# Flight_Controller3.net
KiCad netlist of a schematic drawn in Altium Designer
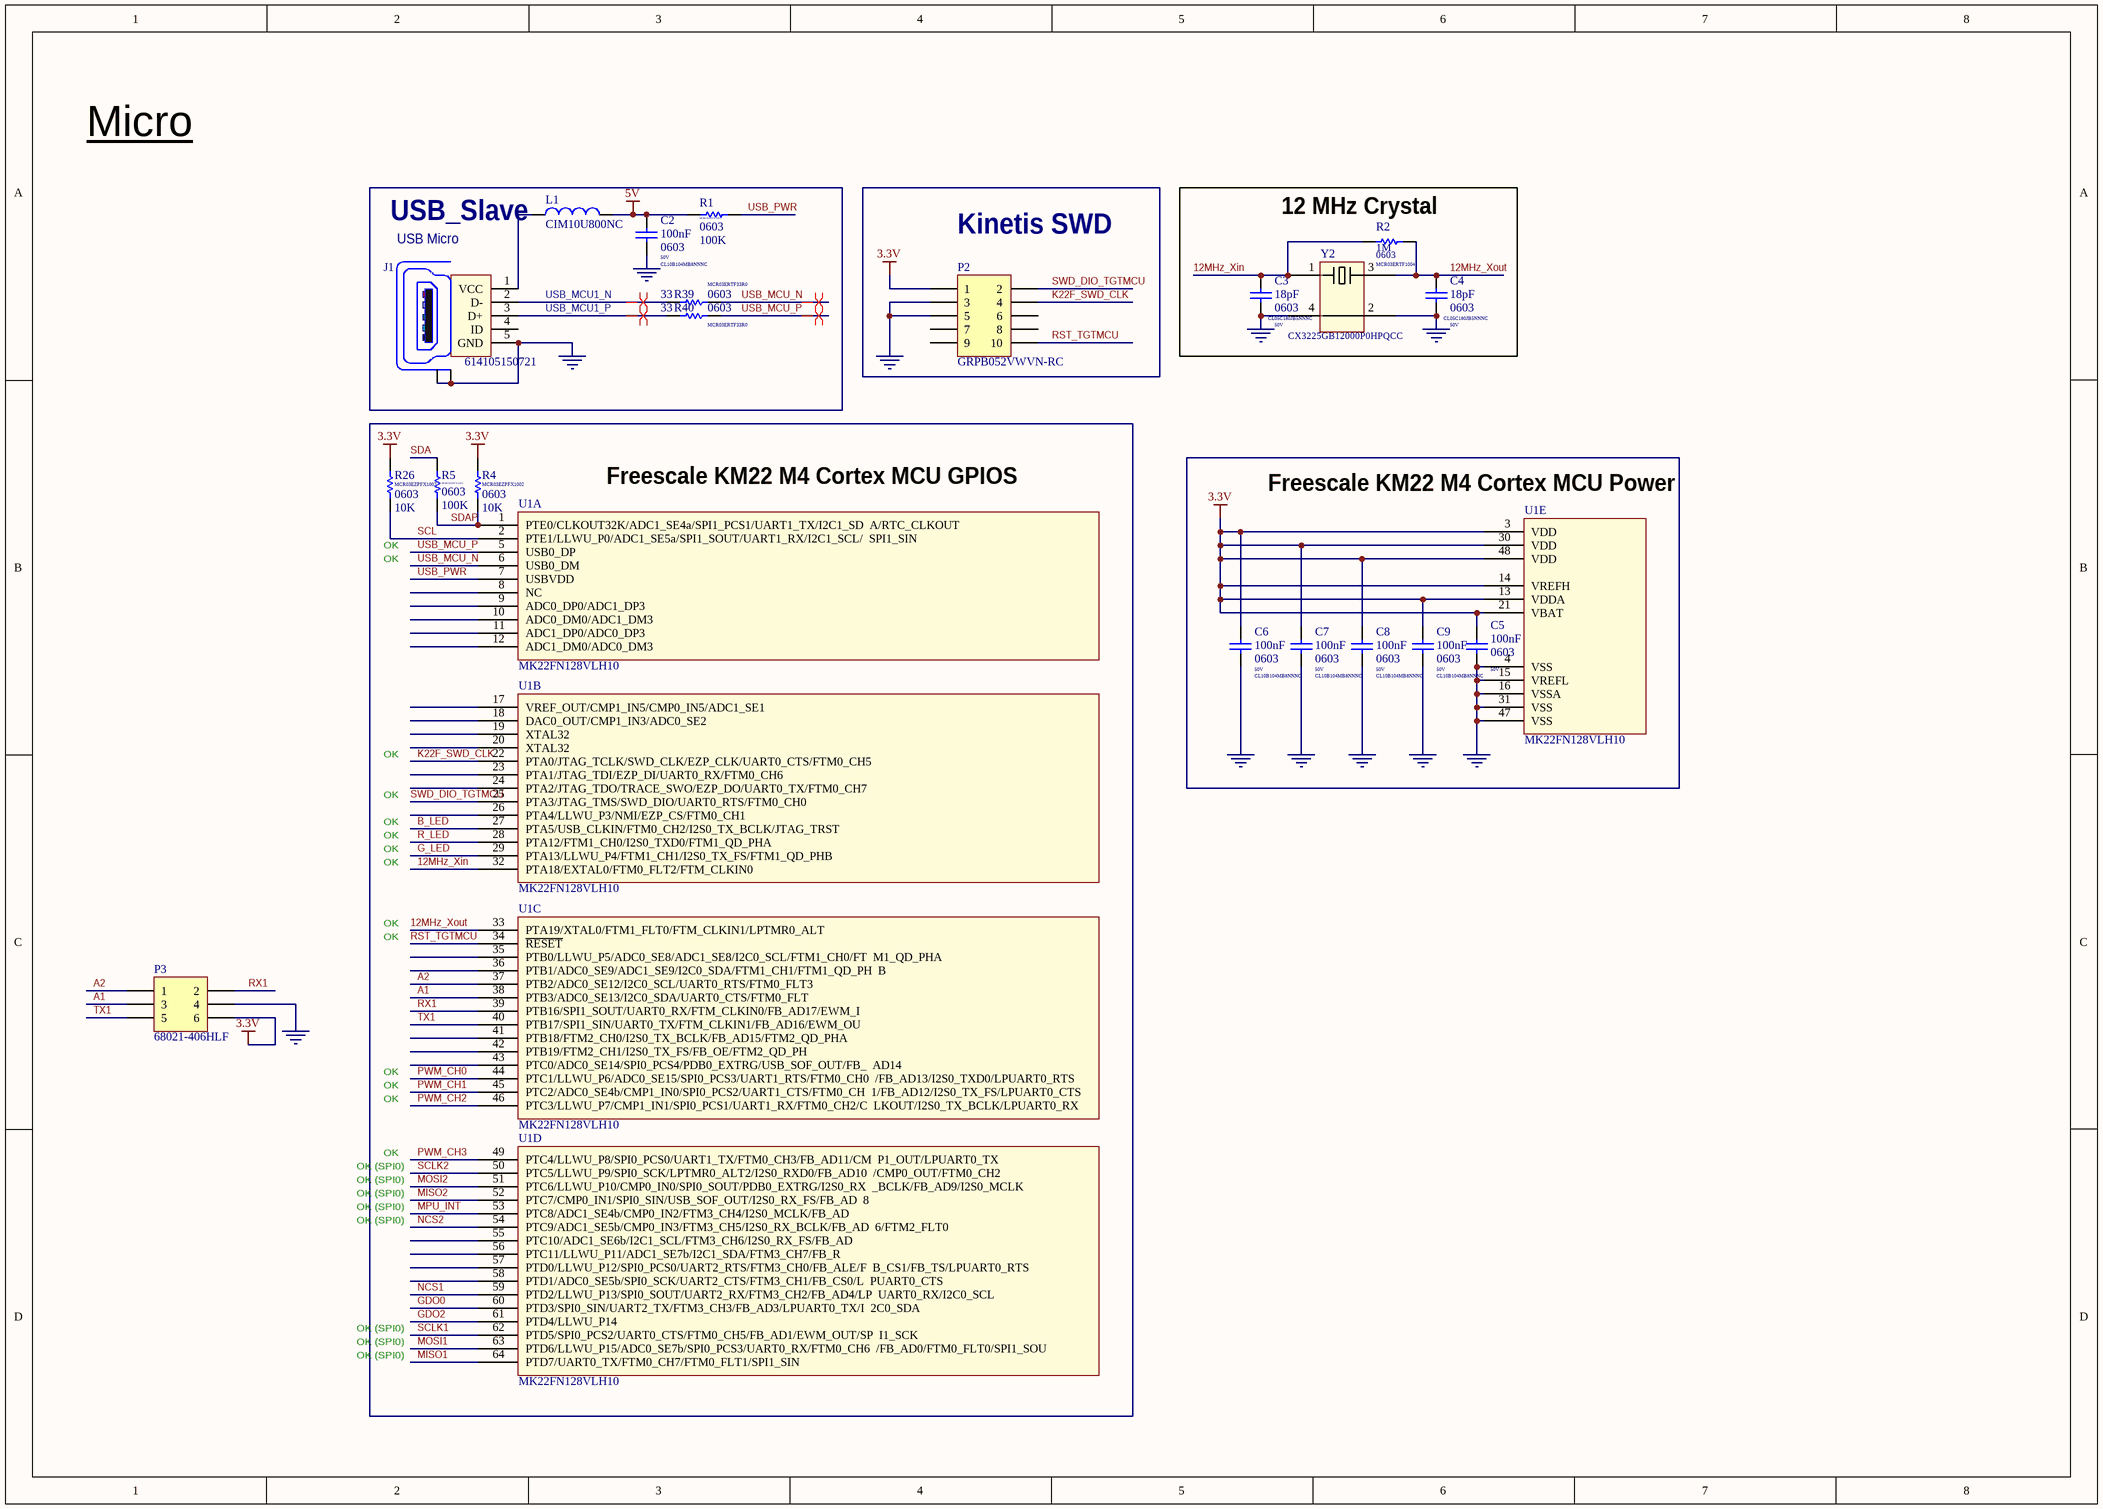
[diagram p0: Flight_Controller3.SchDoc]

(export (version "E")
  (design (tool "Eeschema 10.0.6"))
  (components
    (comp (ref "C2")
      (value "CL10B104MB8NNNC")
      (footprint "1608[0603]C")
      (description "Capacitor (Semiconductor SIM Model)")
      (fields
        (field (name "PACKAGEREFERENCE") "0603")
        (field (name "ALTIUM_VALUE") "100nF")
        (field (name "VOLTAGE") "50V")
      )
      (libsource (lib "Miscellaneous Devices") (part "Cap Semi"))
    )
    (comp (ref "C3")
      (value "CL05C180JB5NNNC")
      (footprint "1608[0603]C")
      (description "Capacitor (Semiconductor SIM Model)")
      (fields
        (field (name "PACKAGEREFERENCE") "0603")
        (field (name "ALTIUM_VALUE") "18pF")
        (field (name "VOLTAGE") "50V")
      )
      (libsource (lib "Miscellaneous Devices") (part "Cap Semi"))
    )
    (comp (ref "C4")
      (value "CL05C180JB5NNNC")
      (footprint "1608[0603]C")
      (description "Capacitor (Semiconductor SIM Model)")
      (fields
        (field (name "PACKAGEREFERENCE") "0603")
        (field (name "ALTIUM_VALUE") "18pF")
        (field (name "VOLTAGE") "50V")
      )
      (libsource (lib "Miscellaneous Devices") (part "Cap Semi"))
    )
    (comp (ref "C5")
      (value "100nF")
      (footprint "1608[0603]C")
      (description "Capacitor (Semiconductor SIM Model)")
      (fields
        (field (name "PACKAGEREFERENCE") "0603")
        (field (name "PART_NUMBER") "CL10B104MB8NNNC")
        (field (name "VOLTAGE") "50V")
      )
      (libsource (lib "Miscellaneous Devices") (part "Cap Semi"))
    )
    (comp (ref "C6")
      (value "CL10B104MB8NNNC")
      (footprint "1608[0603]C")
      (description "Capacitor (Semiconductor SIM Model)")
      (fields
        (field (name "PACKAGEREFERENCE") "0603")
        (field (name "ALTIUM_VALUE") "100nF")
        (field (name "VOLTAGE") "50V")
      )
      (libsource (lib "Miscellaneous Devices") (part "Cap Semi"))
    )
    (comp (ref "C7")
      (value "CL10B104MB8NNNC")
      (footprint "1608[0603]C")
      (description "Capacitor (Semiconductor SIM Model)")
      (fields
        (field (name "PACKAGEREFERENCE") "0603")
        (field (name "ALTIUM_VALUE") "100nF")
        (field (name "VOLTAGE") "50V")
      )
      (libsource (lib "Miscellaneous Devices") (part "Cap Semi"))
    )
    (comp (ref "C8")
      (value "CL10B104MB8NNNC")
      (footprint "1608[0603]C")
      (description "Capacitor (Semiconductor SIM Model)")
      (fields
        (field (name "PACKAGEREFERENCE") "0603")
        (field (name "ALTIUM_VALUE") "100nF")
        (field (name "VOLTAGE") "50V")
      )
      (libsource (lib "Miscellaneous Devices") (part "Cap Semi"))
    )
    (comp (ref "C9")
      (value "CL10B104MB8NNNC")
      (footprint "1608[0603]C")
      (description "Capacitor (Semiconductor SIM Model)")
      (fields
        (field (name "PACKAGEREFERENCE") "0603")
        (field (name "ALTIUM_VALUE") "100nF")
        (field (name "VOLTAGE") "50V")
      )
      (libsource (lib "Miscellaneous Devices") (part "Cap Semi"))
    )
    (comp (ref "J1")
      (value "614105150721")
      (footprint "USB_Micro_Vertical")
      (description "WR-COM_USB_Micro Type B_Vertical_THT")
      (fields
        (field (name "MANUFACTURER") "Würth Elektronik eiSos GmbH")
        (field (name "CREATED BY") "Karrer Zheng")
      )
      (libsource (lib "614105150721") (part "WR-Communication Connectors 614105150721"))
    )
    (comp (ref "L1")
      (value "CIM10U800NC")
      (footprint "1608[0603]L")
      (description "Inductor")
      (libsource (lib "Miscellaneous Devices") (part "Inductor"))
    )
    (comp (ref "P2")
      (value "GRPB052VWVN-RC")
      (footprint "MHDR2X5")
      (description "Header, 5-Pin, Dual row")
      (fields (field (name "PUBLISHER") "Altium Limited"))
      (libsource (lib "Miscellaneous Connectors") (part "Header 5X2"))
    )
    (comp (ref "P3")
      (value "68021-406HLF")
      (footprint "HDR2X3_3D2")
      (description "Header, 3-Pin, Dual row")
      (fields (field (name "PUBLISHER") "Altium Limited"))
      (libsource (lib "Miscellaneous Connectors") (part "Header 3X2"))
    )
    (comp (ref "R1")
      (value "MCR03EZPFX1003")
      (footprint "1608[0603]R")
      (description "Resistor")
      (fields
        (field (name "PACKAGEREFERENCE") "0603")
        (field (name "ALTIUM_VALUE") "100K")
        (field (name "PART_NUMBER") "MCR03ERTJ104")
      )
      (libsource (lib "Miscellaneous Devices") (part "Res1"))
    )
    (comp (ref "R2")
      (value "MCR03ERTF1004")
      (footprint "1608[0603]R")
      (description "Resistor")
      (fields (field (name "ALTIUM_VALUE") "1M") (field (name "PACKAGEREFERENCE") "0603"))
      (libsource (lib "Miscellaneous Devices") (part "Res1"))
    )
    (comp (ref "R4")
      (value "MCR03EZPFX1002")
      (footprint "1608[0603]R")
      (description "Resistor")
      (fields
        (field (name "PACKAGEREFERENCE") "0603")
        (field (name "ALTIUM_VALUE") "10K")
        (field (name "PART_NUMBER") "MCR03ERTJ102")
      )
      (libsource (lib "Miscellaneous Devices") (part "Res1"))
    )
    (comp (ref "R5")
      (value "MCR03EZPFX1003")
      (footprint "1608[0603]R")
      (description "Resistor")
      (fields
        (field (name "PACKAGEREFERENCE") "0603")
        (field (name "ALTIUM_VALUE") "100K")
        (field (name "PART_NUMBER") "MCR03ERTJ104")
      )
      (libsource (lib "Miscellaneous Devices") (part "Res1"))
    )
    (comp (ref "R26")
      (value "MCR03EZPFX1002")
      (footprint "1608[0603]R")
      (description "Resistor")
      (fields
        (field (name "PACKAGEREFERENCE") "0603")
        (field (name "ALTIUM_VALUE") "10K")
        (field (name "PART_NUMBER") "MCR03ERTJ102")
      )
      (libsource (lib "Miscellaneous Devices") (part "Res1"))
    )
    (comp (ref "R39")
      (value "MCR03ERTF33R0")
      (footprint "1608[0603]R")
      (description "Resistor")
      (fields (field (name "PACKAGEREFERENCE") "0603") (field (name "ALTIUM_VALUE") "33"))
      (libsource (lib "Miscellaneous Devices") (part "Res1"))
    )
    (comp (ref "R40")
      (value "MCR03ERTF33R0")
      (footprint "1608[0603]R")
      (description "Resistor")
      (fields
        (field (name "PACKAGEREFERENCE") "0603")
        (field (name "ALTIUM_VALUE") "33")
        (field (name "PART_NUMBER") "MCR03ERTJ102")
      )
      (libsource (lib "Miscellaneous Devices") (part "Res1"))
    )
    (comp (ref "U1")
      (value "MK22FN128VLH10")
      (footprint "LQFP64_10mm_0.5mm")
      (description "MK22FN128VLH10 MCU")
      (libsource (lib "Flight_Controller") (part "MK22FN128VLH10"))
    )
    (comp (ref "Y2")
      (value "CX3225GB12000P0HPQCC")
      (footprint "3225_Crystal")
      (description "12MHz Micro Crystal")
      (libsource (lib "12MHz_micro_crystal") (part "12MHz_Crystal"))
    )
  )
  (nets
    (net (code "1") (name "/12MHz_Xin") (class "Default")
      (node (ref "C3") (pin "2") (pinfunction "2_2") (pintype "passive"))
      (node (ref "R2") (pin "2") (pinfunction "2_2") (pintype "passive"))
      (node (ref "U1") (pin "32") (pinfunction "PTA18/EXTAL0/FTM0_FLT2/FTM_CLKIN0_32") (pintype "passive"))
      (node (ref "Y2") (pin "1") (pinfunction "X1_1") (pintype "passive"))
    )
    (net (code "2") (name "/12MHz_Xout") (class "Default")
      (node (ref "C4") (pin "2") (pinfunction "2_2") (pintype "passive"))
      (node (ref "R2") (pin "1") (pinfunction "1_1") (pintype "passive"))
      (node (ref "U1") (pin "33") (pinfunction "PTA19/XTAL0/FTM1_FLT0/FTM_CLKIN1/LPTMR0_ALT_33") (pintype "passive"))
      (node (ref "Y2") (pin "3") (pinfunction "X2_3") (pintype "passive"))
    )
    (net (code "3") (name "/A1") (class "Default")
      (node (ref "P3") (pin "3") (pinfunction "3_3") (pintype "passive"))
      (node (ref "U1") (pin "38") (pinfunction "PTB3/ADC0_SE13/I2C0_SDA/UART0_CTS/FTM0_FLT_38") (pintype "passive"))
    )
    (net (code "4") (name "/A2") (class "Default")
      (node (ref "P3") (pin "1") (pinfunction "1_1") (pintype "passive"))
      (node (ref "U1") (pin "37") (pinfunction "PTB2/ADC0_SE12/I2C0_SCL/UART0_RTS/FTM0_FLT3_37") (pintype "passive"))
    )
    (net (code "5") (name "/B_LED") (class "Default")
      (node (ref "U1") (pin "27") (pinfunction "PTA5/USB_CLKIN/FTM0_CH2/I2S0_TX_BCLK/JTAG_TRST_27") (pintype "passive"))
    )
    (net (code "6") (name "/GDO0") (class "Default")
      (node (ref "U1") (pin "60") (pinfunction "PTD3/SPI0_SIN/UART2_TX/FTM3_CH3/FB_AD3/LPUART0_TX/I__2C0_SDA_60") (pintype "passive"))
    )
    (net (code "7") (name "/GDO2") (class "Default")
      (node (ref "U1") (pin "61") (pinfunction "PTD4/LLWU_P14_61") (pintype "passive"))
    )
    (net (code "8") (name "/G_LED") (class "Default")
      (node (ref "U1") (pin "29") (pinfunction "PTA13/LLWU_P4/FTM1_CH1/I2S0_TX_FS/FTM1_QD_PHB_29") (pintype "passive"))
    )
    (net (code "9") (name "/K22F_SWD_CLK") (class "Default")
      (node (ref "P2") (pin "4") (pinfunction "4_4") (pintype "passive"))
      (node (ref "U1") (pin "22") (pinfunction "PTA0/JTAG_TCLK/SWD_CLK/EZP_CLK/UART0_CTS/FTM0_CH5_22") (pintype "passive"))
    )
    (net (code "10") (name "/MISO1") (class "Default")
      (node (ref "U1") (pin "64") (pinfunction "PTD7/UART0_TX/FTM0_CH7/FTM0_FLT1/SPI1_SIN_64") (pintype "passive"))
    )
    (net (code "11") (name "/MISO2") (class "Default")
      (node (ref "U1") (pin "52") (pinfunction "PTC7/CMP0_IN1/SPI0_SIN/USB_SOF_OUT/I2S0_RX_FS/FB_AD__8_52") (pintype "passive"))
    )
    (net (code "12") (name "/MOSI1") (class "Default")
      (node (ref "U1") (pin "63") (pinfunction "PTD6/LLWU_P15/ADC0_SE7b/SPI0_PCS3/UART0_RX/FTM0_CH6__/FB_AD0/FTM0_FLT0/SPI1_SOU_63") (pintype "passive"))
    )
    (net (code "13") (name "/MOSI2") (class "Default")
      (node (ref "U1") (pin "51") (pinfunction "PTC6/LLWU_P10/CMP0_IN0/SPI0_SOUT/PDB0_EXTRG/I2S0_RX___BCLK/FB_AD9/I2S0_MCLK_51") (pintype "passive"))
    )
    (net (code "14") (name "/MPU_INT") (class "Default")
      (node (ref "U1") (pin "53") (pinfunction "PTC8/ADC1_SE4b/CMP0_IN2/FTM3_CH4/I2S0_MCLK/FB_AD_53") (pintype "passive"))
    )
    (net (code "15") (name "/NCS1") (class "Default")
      (node (ref "U1") (pin "59") (pinfunction "PTD2/LLWU_P13/SPI0_SOUT/UART2_RX/FTM3_CH2/FB_AD4/LP__UART0_RX/I2C0_SCL_59") (pintype "passive"))
    )
    (net (code "16") (name "/NCS2") (class "Default")
      (node (ref "U1") (pin "54") (pinfunction "PTC9/ADC1_SE5b/CMP0_IN3/FTM3_CH5/I2S0_RX_BCLK/FB_AD__6/FTM2_FLT0_54") (pintype "passive"))
    )
    (net (code "17") (name "/PWM_CH0") (class "Default")
      (node (ref "U1") (pin "44") (pinfunction "PTC1/LLWU_P6/ADC0_SE15/SPI0_PCS3/UART1_RTS/FTM0_CH0__/FB_AD13/I2S0_TXD0/LPUART0_RTS_44") (pintype "passive"))
    )
    (net (code "18") (name "/PWM_CH1") (class "Default")
      (node (ref "U1") (pin "45") (pinfunction "PTC2/ADC0_SE4b/CMP1_IN0/SPI0_PCS2/UART1_CTS/FTM0_CH__1/FB_AD12/I2S0_TX_FS/LPUART0_CTS_45") (pintype "passive"))
    )
    (net (code "19") (name "/PWM_CH2") (class "Default")
      (node (ref "U1") (pin "46") (pinfunction "PTC3/LLWU_P7/CMP1_IN1/SPI0_PCS1/UART1_RX/FTM0_CH2/C__LKOUT/I2S0_TX_BCLK/LPUART0_RX_46") (pintype "passive"))
    )
    (net (code "20") (name "/PWM_CH3") (class "Default")
      (node (ref "U1") (pin "49") (pinfunction "PTC4/LLWU_P8/SPI0_PCS0/UART1_TX/FTM0_CH3/FB_AD11/CM__P1_OUT/LPUART0_TX_49") (pintype "passive"))
    )
    (net (code "21") (name "/RST_TGTMCU") (class "Default")
      (node (ref "P2") (pin "10") (pinfunction "10_10") (pintype "passive"))
      (node (ref "U1") (pin "34") (pinfunction "~{RESET}_34") (pintype "passive"))
    )
    (net (code "22") (name "/RX1") (class "Default")
      (node (ref "P3") (pin "2") (pinfunction "2_2") (pintype "passive"))
      (node (ref "U1") (pin "39") (pinfunction "PTB16/SPI1_SOUT/UART0_RX/FTM_CLKIN0/FB_AD17/EWM_I_39") (pintype "passive"))
    )
    (net (code "23") (name "/R_LED") (class "Default")
      (node (ref "U1") (pin "28") (pinfunction "PTA12/FTM1_CH0/I2S0_TXD0/FTM1_QD_PHA_28") (pintype "passive"))
    )
    (net (code "24") (name "/SCL") (class "Default")
      (node (ref "R26") (pin "1") (pinfunction "1_1") (pintype "passive"))
      (node (ref "U1") (pin "2") (pinfunction "PTE1/LLWU_P0/ADC1_SE5a/SPI1_SOUT/UART1_RX/I2C1_SCL/__SPI1_SIN_2") (pintype "passive"))
    )
    (net (code "25") (name "/SCLK1") (class "Default")
      (node (ref "U1") (pin "62") (pinfunction "PTD5/SPI0_PCS2/UART0_CTS/FTM0_CH5/FB_AD1/EWM_OUT/SP__I1_SCK_62") (pintype "passive"))
    )
    (net (code "26") (name "/SCLK2") (class "Default")
      (node (ref "U1") (pin "50") (pinfunction "PTC5/LLWU_P9/SPI0_SCK/LPTMR0_ALT2/I2S0_RXD0/FB_AD10__/CMP0_OUT/FTM0_CH2_50") (pintype "passive"))
    )
    (net (code "27") (name "/SDA") (class "Default")
      (node (ref "R5") (pin "2") (pinfunction "2_2") (pintype "passive"))
    )
    (net (code "28") (name "/SDAP") (class "Default")
      (node (ref "R4") (pin "1") (pinfunction "1_1") (pintype "passive"))
      (node (ref "R5") (pin "1") (pinfunction "1_1") (pintype "passive"))
      (node (ref "U1") (pin "1") (pinfunction "PTE0/CLKOUT32K/ADC1_SE4a/SPI1_PCS1/UART1_TX/I2C1_SD__A/RTC_CLKOUT_1") (pintype "passive"))
    )
    (net (code "29") (name "/SWD_DIO_TGTMCU") (class "Default")
      (node (ref "P2") (pin "2") (pinfunction "2_2") (pintype "passive"))
      (node (ref "U1") (pin "25") (pinfunction "PTA3/JTAG_TMS/SWD_DIO/UART0_RTS/FTM0_CH0_25") (pintype "passive"))
    )
    (net (code "30") (name "/TX1") (class "Default")
      (node (ref "P3") (pin "5") (pinfunction "5_5") (pintype "passive"))
      (node (ref "U1") (pin "40") (pinfunction "PTB17/SPI1_SIN/UART0_TX/FTM_CLKIN1/FB_AD16/EWM_OU_40") (pintype "passive"))
    )
    (net (code "31") (name "/USB_MCU1_N") (class "Default")
      (node (ref "J1") (pin "2") (pinfunction "D-_2") (pintype "passive"))
      (node (ref "R39") (pin "2") (pinfunction "2_2") (pintype "passive"))
    )
    (net (code "32") (name "/USB_MCU1_P") (class "Default")
      (node (ref "J1") (pin "3") (pinfunction "D+_3") (pintype "passive"))
      (node (ref "R40") (pin "2") (pinfunction "2_2") (pintype "passive"))
    )
    (net (code "33") (name "/USB_MCU_N") (class "Default")
      (node (ref "R39") (pin "1") (pinfunction "1_1") (pintype "passive"))
      (node (ref "U1") (pin "6") (pinfunction "USB0_DM_6") (pintype "passive"))
    )
    (net (code "34") (name "/USB_MCU_P") (class "Default")
      (node (ref "R40") (pin "1") (pinfunction "1_1") (pintype "passive"))
      (node (ref "U1") (pin "5") (pinfunction "USB0_DP_5") (pintype "passive"))
    )
    (net (code "35") (name "/USB_PWR") (class "Default")
      (node (ref "R1") (pin "2") (pinfunction "2_2") (pintype "passive"))
      (node (ref "U1") (pin "7") (pinfunction "USBVDD_7") (pintype "passive"))
    )
    (net (code "36") (name "3.3V") (class "Default")
      (node (ref "C5") (pin "2") (pinfunction "2_2") (pintype "passive"))
      (node (ref "C6") (pin "2") (pinfunction "2_2") (pintype "passive"))
      (node (ref "C7") (pin "2") (pinfunction "2_2") (pintype "passive"))
      (node (ref "C8") (pin "2") (pinfunction "2_2") (pintype "passive"))
      (node (ref "C9") (pin "2") (pinfunction "2_2") (pintype "passive"))
      (node (ref "P2") (pin "1") (pinfunction "1_1") (pintype "passive"))
      (node (ref "P3") (pin "6") (pinfunction "6_6") (pintype "passive"))
      (node (ref "R26") (pin "2") (pinfunction "2_2") (pintype "passive"))
      (node (ref "R4") (pin "2") (pinfunction "2_2") (pintype "passive"))
      (node (ref "U1") (pin "13") (pinfunction "VDDA_13") (pintype "passive"))
      (node (ref "U1") (pin "14") (pinfunction "VREFH_14") (pintype "passive"))
      (node (ref "U1") (pin "21") (pinfunction "VBAT_21") (pintype "passive"))
      (node (ref "U1") (pin "3") (pinfunction "VDD_3") (pintype "passive"))
      (node (ref "U1") (pin "30") (pinfunction "VDD_30") (pintype "passive"))
      (node (ref "U1") (pin "48") (pinfunction "VDD_48") (pintype "passive"))
    )
    (net (code "37") (name "5V") (class "Default")
      (node (ref "C2") (pin "2") (pinfunction "2_2") (pintype "passive"))
      (node (ref "L1") (pin "1") (pinfunction "1_1") (pintype "passive"))
      (node (ref "R1") (pin "1") (pinfunction "1_1") (pintype "passive"))
    )
    (net (code "38") (name "GND") (class "Default")
      (node (ref "C2") (pin "1") (pinfunction "1_1") (pintype "passive"))
      (node (ref "C3") (pin "1") (pinfunction "1_1") (pintype "passive"))
      (node (ref "C4") (pin "1") (pinfunction "1_1") (pintype "passive"))
      (node (ref "C5") (pin "1") (pinfunction "1_1") (pintype "passive"))
      (node (ref "C6") (pin "1") (pinfunction "1_1") (pintype "passive"))
      (node (ref "C7") (pin "1") (pinfunction "1_1") (pintype "passive"))
      (node (ref "C8") (pin "1") (pinfunction "1_1") (pintype "passive"))
      (node (ref "C9") (pin "1") (pinfunction "1_1") (pintype "passive"))
      (node (ref "J1") (pin "5") (pinfunction "GND_5") (pintype "passive"))
      (node (ref "J1") (pin "Z1") (pinfunction "Shield_Z1") (pintype "passive"))
      (node (ref "J1") (pin "Z2") (pinfunction "Shield_Z2") (pintype "passive"))
      (node (ref "P2") (pin "3") (pinfunction "3_3") (pintype "passive"))
      (node (ref "P2") (pin "5") (pinfunction "5_5") (pintype "passive"))
      (node (ref "P3") (pin "4") (pinfunction "4_4") (pintype "passive"))
      (node (ref "U1") (pin "15") (pinfunction "VREFL_15") (pintype "passive"))
      (node (ref "U1") (pin "16") (pinfunction "VSSA_16") (pintype "passive"))
      (node (ref "U1") (pin "31") (pinfunction "VSS_31") (pintype "passive"))
      (node (ref "U1") (pin "4") (pinfunction "VSS_4") (pintype "passive"))
      (node (ref "U1") (pin "47") (pinfunction "VSS_47") (pintype "passive"))
      (node (ref "Y2") (pin "2") (pinfunction "GND_2") (pintype "passive"))
      (node (ref "Y2") (pin "4") (pinfunction "GND_4") (pintype "passive"))
    )
    (net (code "39") (name "Net-(J1-VCC)") (class "Default")
      (node (ref "J1") (pin "1") (pinfunction "VCC_1") (pintype "passive"))
      (node (ref "L1") (pin "2") (pinfunction "2_2") (pintype "passive"))
    )
    (net (code "40") (name "unconnected-(J1-ID-Pad4)") (class "Default")
      (node (ref "J1") (pin "4") (pinfunction "ID_4") (pintype "passive"))
    )
    (net (code "41") (name "unconnected-(P2-Pad6)") (class "Default")
      (node (ref "P2") (pin "6") (pinfunction "6_6") (pintype "passive"))
    )
    (net (code "42") (name "unconnected-(P2-Pad7)") (class "Default")
      (node (ref "P2") (pin "7") (pinfunction "7_7") (pintype "passive"))
    )
    (net (code "43") (name "unconnected-(P2-Pad8)") (class "Default")
      (node (ref "P2") (pin "8") (pinfunction "8_8") (pintype "passive"))
    )
    (net (code "44") (name "unconnected-(P2-Pad9)") (class "Default")
      (node (ref "P2") (pin "9") (pinfunction "9_9") (pintype "passive"))
    )
    (net (code "45") (name "unconnected-(U1A-ADC0_DM0{slash}ADC1_DM3-Pad10)") (class "Default")
      (node (ref "U1") (pin "10") (pinfunction "ADC0_DM0/ADC1_DM3_10") (pintype "passive"))
    )
    (net (code "46") (name "unconnected-(U1A-ADC0_DP0{slash}ADC1_DP3-Pad9)") (class "Default")
      (node (ref "U1") (pin "9") (pinfunction "ADC0_DP0/ADC1_DP3_9") (pintype "passive"))
    )
    (net (code "47") (name "unconnected-(U1A-ADC1_DM0{slash}ADC0_DM3-Pad12)") (class "Default")
      (node (ref "U1") (pin "12") (pinfunction "ADC1_DM0/ADC0_DM3_12") (pintype "passive"))
    )
    (net (code "48") (name "unconnected-(U1A-ADC1_DP0{slash}ADC0_DP3-Pad11)") (class "Default")
      (node (ref "U1") (pin "11") (pinfunction "ADC1_DP0/ADC0_DP3_11") (pintype "passive"))
    )
    (net (code "49") (name "unconnected-(U1A-NC-Pad8)") (class "Default")
      (node (ref "U1") (pin "8") (pinfunction "NC_8") (pintype "passive"))
    )
    (net (code "50") (name "unconnected-(U1B-DAC0_OUT{slash}CMP1_IN3{slash}ADC0_SE2-Pad18)") (class "Default")
      (node (ref "U1") (pin "18") (pinfunction "DAC0_OUT/CMP1_IN3/ADC0_SE2_18") (pintype "passive"))
    )
    (net (code "51") (name "unconnected-(U1B-PTA1{slash}JTAG_TDI{slash}EZP_DI{slash}UART0_RX{slash}FTM0_CH6-Pad23)") (class "Default")
      (node (ref "U1") (pin "23") (pinfunction "PTA1/JTAG_TDI/EZP_DI/UART0_RX/FTM0_CH6_23") (pintype "passive"))
    )
    (net (code "52") (name "unconnected-(U1B-PTA2{slash}JTAG_TDO{slash}TRACE_SWO{slash}EZP_DO{slash}UART0_TX{slash}FTM0_CH7-Pad24)") (class "Default")
      (node (ref "U1") (pin "24") (pinfunction "PTA2/JTAG_TDO/TRACE_SWO/EZP_DO/UART0_TX/FTM0_CH7_24") (pintype "passive"))
    )
    (net (code "53") (name "unconnected-(U1B-PTA4{slash}LLWU_P3{slash}NMI{slash}EZP_CS{slash}FTM0_CH-Pad26)") (class "Default")
      (node (ref "U1") (pin "26") (pinfunction "PTA4/LLWU_P3/NMI/EZP_CS/FTM0_CH_26") (pintype "passive"))
    )
    (net (code "54") (name "unconnected-(U1B-VREF_OUT{slash}CMP1_IN5{slash}CMP0_IN5{slash}ADC1_SE1-Pad17)") (class "Default")
      (node (ref "U1") (pin "17") (pinfunction "VREF_OUT/CMP1_IN5/CMP0_IN5/ADC1_SE1_17") (pintype "passive"))
    )
    (net (code "55") (name "unconnected-(U1B-XTAL32-Pad19)") (class "Default")
      (node (ref "U1") (pin "19") (pinfunction "XTAL32_19") (pintype "passive"))
    )
    (net (code "56") (name "unconnected-(U1B-XTAL32-Pad20)") (class "Default")
      (node (ref "U1") (pin "20") (pinfunction "XTAL32_20") (pintype "passive"))
    )
    (net (code "57") (name "unconnected-(U1C-PTB0{slash}LLWU_P5{slash}ADC0_SE8{slash}ADC1_SE8{slash}I2C0_SCL{slash}FTM1_CH0{slash}FT__M1_QD_PHA-Pad35)") (class "Default")
      (node (ref "U1") (pin "35") (pinfunction "PTB0/LLWU_P5/ADC0_SE8/ADC1_SE8/I2C0_SCL/FTM1_CH0/FT__M1_QD_PHA_35") (pintype "passive"))
    )
    (net (code "58") (name "unconnected-(U1C-PTB1{slash}ADC0_SE9{slash}ADC1_SE9{slash}I2C0_SDA{slash}FTM1_CH1{slash}FTM1_QD_PH__B-Pad36)") (class "Default")
      (node (ref "U1") (pin "36") (pinfunction "PTB1/ADC0_SE9/ADC1_SE9/I2C0_SDA/FTM1_CH1/FTM1_QD_PH__B_36") (pintype "passive"))
    )
    (net (code "59") (name "unconnected-(U1C-PTB18{slash}FTM2_CH0{slash}I2S0_TX_BCLK{slash}FB_AD15{slash}FTM2_QD_PHA-Pad41)") (class "Default")
      (node (ref "U1") (pin "41") (pinfunction "PTB18/FTM2_CH0/I2S0_TX_BCLK/FB_AD15/FTM2_QD_PHA_41") (pintype "passive"))
    )
    (net (code "60") (name "unconnected-(U1C-PTB19{slash}FTM2_CH1{slash}I2S0_TX_FS{slash}FB_OE{slash}FTM2_QD_PH-Pad42)") (class "Default")
      (node (ref "U1") (pin "42") (pinfunction "PTB19/FTM2_CH1/I2S0_TX_FS/FB_OE/FTM2_QD_PH_42") (pintype "passive"))
    )
    (net (code "61") (name "unconnected-(U1C-PTC0{slash}ADC0_SE14{slash}SPI0_PCS4{slash}PDB0_EXTRG{slash}USB_SOF_OUT{slash}FB___AD14-Pad43)") (class "Default")
      (node (ref "U1") (pin "43") (pinfunction "PTC0/ADC0_SE14/SPI0_PCS4/PDB0_EXTRG/USB_SOF_OUT/FB___AD14_43") (pintype "passive"))
    )
    (net (code "62") (name "unconnected-(U1D-PTC10{slash}ADC1_SE6b{slash}I2C1_SCL{slash}FTM3_CH6{slash}I2S0_RX_FS{slash}FB_AD-Pad55)") (class "Default")
      (node (ref "U1") (pin "55") (pinfunction "PTC10/ADC1_SE6b/I2C1_SCL/FTM3_CH6/I2S0_RX_FS/FB_AD_55") (pintype "passive"))
    )
    (net (code "63") (name "unconnected-(U1D-PTC11{slash}LLWU_P11{slash}ADC1_SE7b{slash}I2C1_SDA{slash}FTM3_CH7{slash}FB_R-Pad56)") (class "Default")
      (node (ref "U1") (pin "56") (pinfunction "PTC11/LLWU_P11/ADC1_SE7b/I2C1_SDA/FTM3_CH7/FB_R_56") (pintype "passive"))
    )
    (net (code "64") (name "unconnected-(U1D-PTD0{slash}LLWU_P12{slash}SPI0_PCS0{slash}UART2_RTS{slash}FTM3_CH0{slash}FB_ALE{slash}F__B_CS1{slash}FB_TS{slash}LPUART0_RTS-Pad57)") (class "Default")
      (node (ref "U1") (pin "57") (pinfunction "PTD0/LLWU_P12/SPI0_PCS0/UART2_RTS/FTM3_CH0/FB_ALE/F__B_CS1/FB_TS/LPUART0_RTS_57") (pintype "passive"))
    )
    (net (code "65") (name "unconnected-(U1D-PTD1{slash}ADC0_SE5b{slash}SPI0_SCK{slash}UART2_CTS{slash}FTM3_CH1{slash}FB_CS0{slash}L__PUART0_CTS-Pad58)") (class "Default")
      (node (ref "U1") (pin "58") (pinfunction "PTD1/ADC0_SE5b/SPI0_SCK/UART2_CTS/FTM3_CH1/FB_CS0/L__PUART0_CTS_58") (pintype "passive"))
    )
  )
)
